# 05_-_MicroSD.net
KiCad netlist of a schematic drawn in Altium Designer
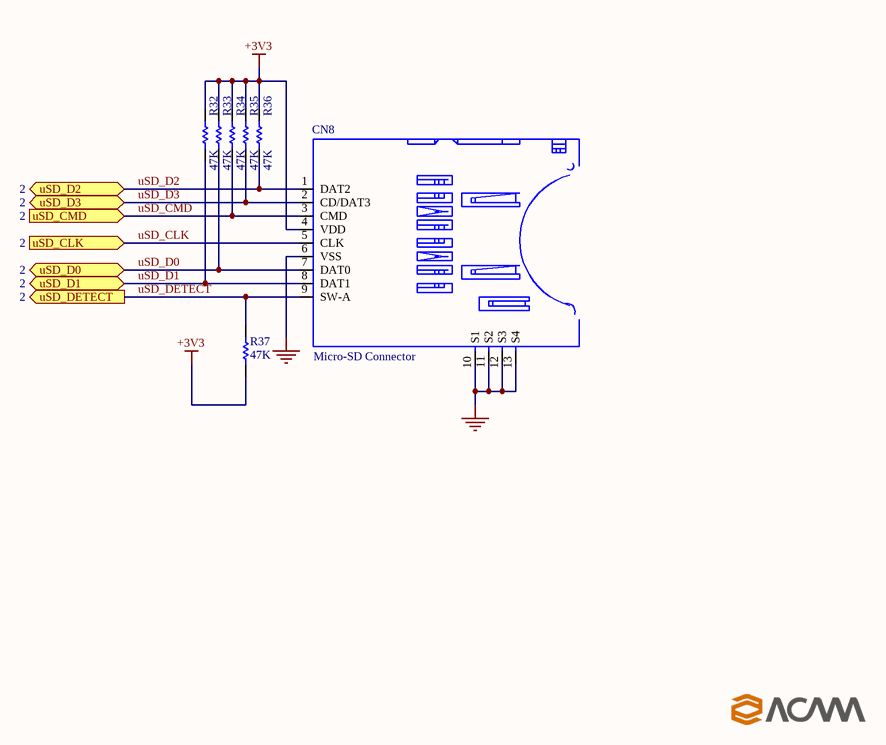
[diagram p0: [05] - MicroSD.SchDoc]

(export (version "E")
  (design (tool "Eeschema 10.0.6"))
  (components
    (comp (ref "CN8")
      (value "Micro-SD Connector")
      (footprint "MICRO_SD_TFP-09-2-12B")
      (description "Javanelec 1.10mm Pitch microSD Memory Card Connector. Push-Push")
      (fields (field (name "MANUFACTURER PART NUM") "TFP-09-2-12B"))
      (libsource (lib "Farzan Custom Library") (part "MicroSD_Connector #2"))
    )
    (comp (ref "R32")
      (value "47K")
      (footprint "0805_R")
      (description "SMD Resistor")
      (fields (field (name "TOLERANCE") "5%"))
      (libsource (lib "Farzan Custom Library") (part "Res SMD"))
    )
    (comp (ref "R33")
      (value "47K")
      (footprint "0805_R")
      (description "SMD Resistor")
      (fields (field (name "TOLERANCE") "5%"))
      (libsource (lib "Farzan Custom Library") (part "Res SMD"))
    )
    (comp (ref "R34")
      (value "47K")
      (footprint "0805_R")
      (description "SMD Resistor")
      (fields (field (name "TOLERANCE") "5%"))
      (libsource (lib "Farzan Custom Library") (part "Res SMD"))
    )
    (comp (ref "R35")
      (value "47K")
      (footprint "0805_R")
      (description "SMD Resistor")
      (fields (field (name "TOLERANCE") "5%"))
      (libsource (lib "Farzan Custom Library") (part "Res SMD"))
    )
    (comp (ref "R36")
      (value "47K")
      (footprint "0805_R")
      (description "SMD Resistor")
      (fields (field (name "TOLERANCE") "5%"))
      (libsource (lib "Farzan Custom Library") (part "Res SMD"))
    )
    (comp (ref "R37")
      (value "47K")
      (footprint "0805_R")
      (description "SMD Resistor")
      (fields (field (name "TOLERANCE") "5%"))
      (libsource (lib "Farzan Custom Library") (part "Res SMD"))
    )
  )
  (nets
    (net (code "1") (name "+3V3") (class "Default")
      (node (ref "CN8") (pin "4") (pinfunction "VDD_4") (pintype "passive"))
      (node (ref "R32") (pin "2") (pinfunction "2_2") (pintype "passive"))
      (node (ref "R33") (pin "2") (pinfunction "2_2") (pintype "passive"))
      (node (ref "R34") (pin "2") (pinfunction "2_2") (pintype "passive"))
      (node (ref "R35") (pin "2") (pinfunction "2_2") (pintype "passive"))
      (node (ref "R36") (pin "2") (pinfunction "2_2") (pintype "passive"))
      (node (ref "R37") (pin "1") (pinfunction "1_1") (pintype "passive"))
    )
    (net (code "2") (name "/uSD_CLK") (class "Default")
      (node (ref "CN8") (pin "5") (pinfunction "CLK_5") (pintype "passive"))
    )
    (net (code "3") (name "/uSD_CMD") (class "Default")
      (node (ref "CN8") (pin "3") (pinfunction "CMD_3") (pintype "passive"))
      (node (ref "R34") (pin "1") (pinfunction "1_1") (pintype "passive"))
    )
    (net (code "4") (name "/uSD_D0") (class "Default")
      (node (ref "CN8") (pin "7") (pinfunction "DAT0_7") (pintype "passive"))
      (node (ref "R33") (pin "1") (pinfunction "1_1") (pintype "passive"))
    )
    (net (code "5") (name "/uSD_D1") (class "Default")
      (node (ref "CN8") (pin "8") (pinfunction "DAT1_8") (pintype "passive"))
      (node (ref "R32") (pin "1") (pinfunction "1_1") (pintype "passive"))
    )
    (net (code "6") (name "/uSD_D2") (class "Default")
      (node (ref "CN8") (pin "1") (pinfunction "DAT2_1") (pintype "passive"))
      (node (ref "R36") (pin "1") (pinfunction "1_1") (pintype "passive"))
    )
    (net (code "7") (name "/uSD_D3") (class "Default")
      (node (ref "CN8") (pin "2") (pinfunction "CD/DAT3_2") (pintype "passive"))
      (node (ref "R35") (pin "1") (pinfunction "1_1") (pintype "passive"))
    )
    (net (code "8") (name "/uSD_DETECT") (class "Default")
      (node (ref "CN8") (pin "9") (pinfunction "SW-A_9") (pintype "passive"))
      (node (ref "R37") (pin "2") (pinfunction "2_2") (pintype "passive"))
    )
    (net (code "9") (name "GND") (class "Default")
      (node (ref "CN8") (pin "10") (pinfunction "S1_10") (pintype "passive"))
      (node (ref "CN8") (pin "11") (pinfunction "S2_11") (pintype "passive"))
      (node (ref "CN8") (pin "12") (pinfunction "S3_12") (pintype "passive"))
      (node (ref "CN8") (pin "13") (pinfunction "S4_13") (pintype "passive"))
      (node (ref "CN8") (pin "6") (pinfunction "VSS_6") (pintype "passive"))
    )
  )
)
